# sb-sonata-headers1.net
KiCad netlist of a schematic drawn in Altium Designer
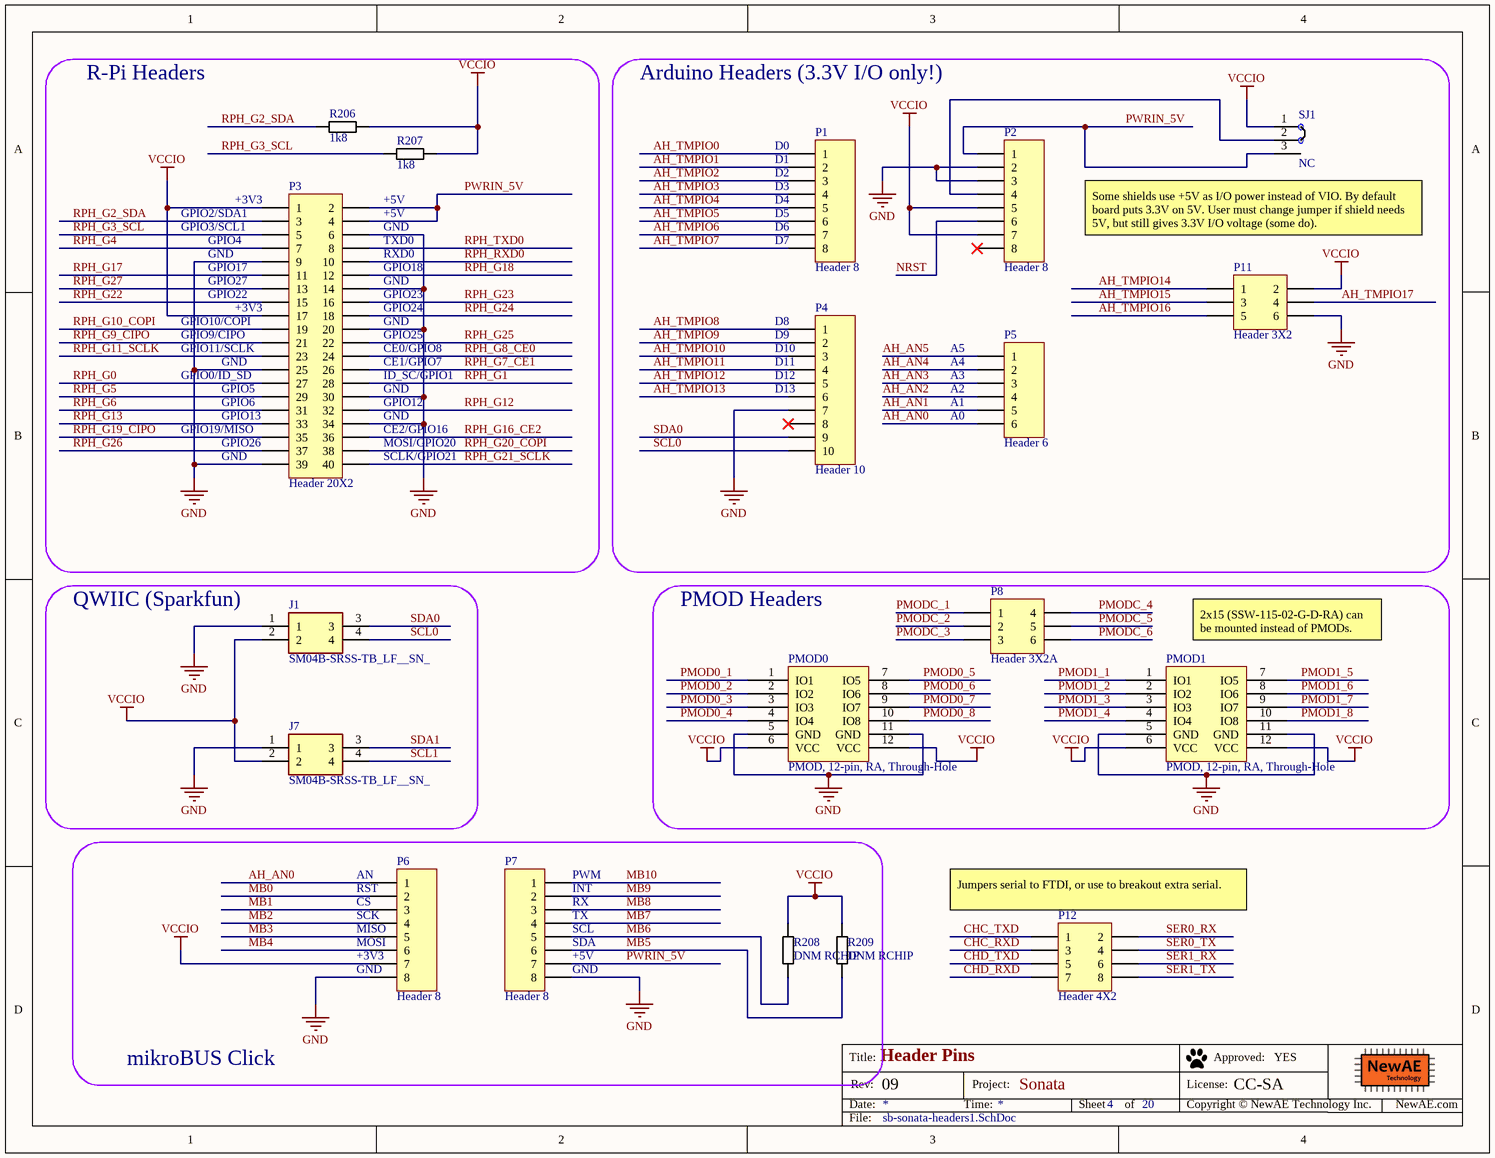
[diagram p0: sb-sonata-headers1.SchDoc]

(export (version "E")
  (design (tool "Eeschema 10.0.6"))
  (components
    (comp (ref "J1")
      (value "SM04B-SRSS-TB_LF__SN_")
      (footprint "SM04B-SRSS-TB(LFSN)")
      (description "Connector")
      (fields (field (name "MANUFACTURER_PART_NUMBER") "SM04B-SRSS-TB(LF)(SN)"))
      (libsource (lib "*") (part "SM04B-SRSS-TB_LF__SN_"))
    )
    (comp (ref "J7")
      (value "SM04B-SRSS-TB_LF__SN_")
      (footprint "SM04B-SRSS-TB(LFSN)")
      (description "Connector")
      (fields (field (name "MANUFACTURER_PART_NUMBER") "SM04B-SRSS-TB(LF)(SN)"))
      (libsource (lib "*") (part "SM04B-SRSS-TB_LF__SN_"))
    )
    (comp (ref "P1")
      (value "Header 8")
      (footprint "HDR1X8_SLW-108-01-T-S")
      (description "Header, 8-Pin")
      (fields (field (name "PUBLISHER") "Altium Limited"))
      (libsource (lib "") (part "Header 8_1"))
    )
    (comp (ref "P2")
      (value "Header 8")
      (footprint "HDR1X8_SLW-108-01-T-S")
      (description "Header, 8-Pin")
      (fields (field (name "PUBLISHER") "Altium Limited"))
      (libsource (lib "") (part "Header 8_1"))
    )
    (comp (ref "P3")
      (value "Header 20X2")
      (footprint "HDR2X20_861400402YO2LF")
      (description "Header, 20-Pin, Dual row")
      (fields (field (name "PUBLISHER") "Altium Limited"))
      (libsource (lib "Miscellaneous Connectors") (part "Header 20X2"))
    )
    (comp (ref "P4")
      (value "Header 10")
      (footprint "HDR1X10_SLW-110-01-T-S")
      (description "Header, 10-Pin")
      (fields (field (name "PUBLISHER") "Altium Limited"))
      (libsource (lib "Miscellaneous Connectors") (part "Header 10"))
    )
    (comp (ref "P5")
      (value "Header 6")
      (footprint "HDR1X6_SLW-106-01-T-S")
      (description "Header, 6-Pin")
      (fields (field (name "PUBLISHER") "Altium Limited"))
      (libsource (lib "Miscellaneous Connectors") (part "Header 6"))
    )
    (comp (ref "P6")
      (value "Header 8")
      (footprint "HDR1X8_SLW-108-01-T-S")
      (description "Header, 8-Pin")
      (fields (field (name "PUBLISHER") "Altium Limited"))
      (libsource (lib "") (part "Header 8_1"))
    )
    (comp (ref "P7")
      (value "Header 8")
      (footprint "HDR1X8_SLW-108-01-T-S")
      (description "Header, 8-Pin")
      (fields (field (name "PUBLISHER") "Altium Limited"))
      (libsource (lib "Miscellaneous Connectors") (part "Header 8"))
    )
    (comp (ref "P8")
      (value "Header 3X2A")
      (footprint "HDR2X3_CEN")
      (description "Header, 3-Pin, Dual row")
      (fields (field (name "PUBLISHER") "Altium Limited"))
      (libsource (lib "Miscellaneous Connectors") (part "Header 3X2A"))
    )
    (comp (ref "P11")
      (value "Header 3X2")
      (footprint "HDR2X3_XG8T-0641")
      (description "Header, 3-Pin, Dual row")
      (fields (field (name "PUBLISHER") "Altium Limited"))
      (libsource (lib "Miscellaneous Connectors") (part "Header 3X2"))
    )
    (comp (ref "P12")
      (value "Header 4X2")
      (footprint "HDR2X4_XG8T-0841")
      (description "Header, 4-Pin, Dual row")
      (fields (field (name "PUBLISHER") "Altium Limited"))
      (libsource (lib "Miscellaneous Connectors") (part "Header 4X2"))
    )
    (comp (ref "PMOD0")
      (value "PMOD, 12-pin, RA, Through-Hole")
      (footprint "SAMTEC_SSW_106_02_X_D_RA_PMOD")
      (fields (field (name "PART NUMBER") "PMOD_2ROW_FEMALERATH"))
      (libsource (lib "NewAE_AltiumLib") (part "12PIN_RA_FEMALE"))
    )
    (comp (ref "PMOD1")
      (value "PMOD, 12-pin, RA, Through-Hole")
      (footprint "SAMTEC_SSW_106_02_X_D_RA_PMOD")
      (fields (field (name "PART NUMBER") "PMOD_2ROW_FEMALERATH"))
      (libsource (lib "NewAE_AltiumLib") (part "12PIN_RA_FEMALE"))
    )
    (comp (ref "R206")
      (value "1k8")
      (footprint "RESC1608X55N")
      (description "1k8 res, 0603, 1%, 1/10W")
      (fields (field (name "PART NUMBER") "RCHIP-1K8-0603") (field (name "TOLERANCE") "1%"))
      (libsource (lib "") (part "RES-EU_1"))
    )
    (comp (ref "R207")
      (value "1k8")
      (footprint "RESC1608X55N")
      (description "1k8 res, 0603, 1%, 1/10W")
      (fields (field (name "PART NUMBER") "RCHIP-1K8-0603") (field (name "TOLERANCE") "1%"))
      (libsource (lib "") (part "RES-EU_1"))
    )
    (comp (ref "R208")
      (value "DNM RCHIP")
      (footprint "RESC1608X55N")
      (description "Do Not Mount Resistor")
      (fields (field (name "PART NUMBER") "RCHIP-DNM-0603"))
      (libsource (lib "NewAE_AltiumLib") (part "RES-EU"))
    )
    (comp (ref "R209")
      (value "DNM RCHIP")
      (footprint "RESC1608X55N")
      (description "Do Not Mount Resistor")
      (fields (field (name "PART NUMBER") "RCHIP-DNM-0603"))
      (libsource (lib "NewAE_AltiumLib") (part "RES-EU"))
    )
    (comp (ref "SJ1")
      (value "NC")
      (footprint "SJ_3S_NC12")
      (description "Solder Jumper, NC")
      (fields (field (name "PART NUMBER") "SJ_3S_12JMP"))
      (libsource (lib "NewAE_AltiumLib") (part "SJ_3S_12JMP"))
    )
  )
  (nets
    (net (code "1") (name "/AH_AN0") (class "Default")
      (node (ref "P5") (pin "6") (pinfunction "6_6") (pintype "passive"))
      (node (ref "P6") (pin "1") (pinfunction "1_1") (pintype "passive"))
    )
    (net (code "2") (name "/AH_AN1") (class "Default")
      (node (ref "P5") (pin "5") (pinfunction "5_5") (pintype "passive"))
    )
    (net (code "3") (name "/AH_AN2") (class "Default")
      (node (ref "P5") (pin "4") (pinfunction "4_4") (pintype "passive"))
    )
    (net (code "4") (name "/AH_AN3") (class "Default")
      (node (ref "P5") (pin "3") (pinfunction "3_3") (pintype "passive"))
    )
    (net (code "5") (name "/AH_AN4") (class "Default")
      (node (ref "P5") (pin "2") (pinfunction "2_2") (pintype "passive"))
    )
    (net (code "6") (name "/AH_AN5") (class "Default")
      (node (ref "P5") (pin "1") (pinfunction "1_1") (pintype "passive"))
    )
    (net (code "7") (name "/AH_TMPIO0") (class "Default")
      (node (ref "P1") (pin "1") (pinfunction "1_1") (pintype "passive"))
    )
    (net (code "8") (name "/AH_TMPIO1") (class "Default")
      (node (ref "P1") (pin "2") (pinfunction "2_2") (pintype "passive"))
    )
    (net (code "9") (name "/AH_TMPIO2") (class "Default")
      (node (ref "P1") (pin "3") (pinfunction "3_3") (pintype "passive"))
    )
    (net (code "10") (name "/AH_TMPIO3") (class "Default")
      (node (ref "P1") (pin "4") (pinfunction "4_4") (pintype "passive"))
    )
    (net (code "11") (name "/AH_TMPIO4") (class "Default")
      (node (ref "P1") (pin "5") (pinfunction "5_5") (pintype "passive"))
    )
    (net (code "12") (name "/AH_TMPIO5") (class "Default")
      (node (ref "P1") (pin "6") (pinfunction "6_6") (pintype "passive"))
    )
    (net (code "13") (name "/AH_TMPIO6") (class "Default")
      (node (ref "P1") (pin "7") (pinfunction "7_7") (pintype "passive"))
    )
    (net (code "14") (name "/AH_TMPIO7") (class "Default")
      (node (ref "P1") (pin "8") (pinfunction "8_8") (pintype "passive"))
    )
    (net (code "15") (name "/AH_TMPIO8") (class "Default")
      (node (ref "P4") (pin "1") (pinfunction "1_1") (pintype "passive"))
    )
    (net (code "16") (name "/AH_TMPIO9") (class "Default")
      (node (ref "P4") (pin "2") (pinfunction "2_2") (pintype "passive"))
    )
    (net (code "17") (name "/AH_TMPIO10") (class "Default")
      (node (ref "P4") (pin "3") (pinfunction "3_3") (pintype "passive"))
    )
    (net (code "18") (name "/AH_TMPIO11") (class "Default")
      (node (ref "P4") (pin "4") (pinfunction "4_4") (pintype "passive"))
    )
    (net (code "19") (name "/AH_TMPIO12") (class "Default")
      (node (ref "P4") (pin "5") (pinfunction "5_5") (pintype "passive"))
    )
    (net (code "20") (name "/AH_TMPIO13") (class "Default")
      (node (ref "P4") (pin "6") (pinfunction "6_6") (pintype "passive"))
    )
    (net (code "21") (name "/AH_TMPIO14") (class "Default")
      (node (ref "P11") (pin "1") (pinfunction "1_1") (pintype "passive"))
    )
    (net (code "22") (name "/AH_TMPIO15") (class "Default")
      (node (ref "P11") (pin "3") (pinfunction "3_3") (pintype "passive"))
    )
    (net (code "23") (name "/AH_TMPIO16") (class "Default")
      (node (ref "P11") (pin "5") (pinfunction "5_5") (pintype "passive"))
    )
    (net (code "24") (name "/AH_TMPIO17") (class "Default")
      (node (ref "P11") (pin "4") (pinfunction "4_4") (pintype "passive"))
    )
    (net (code "25") (name "/CHC_RXD") (class "Default")
      (node (ref "P12") (pin "3") (pinfunction "3_3") (pintype "passive"))
    )
    (net (code "26") (name "/CHC_TXD") (class "Default")
      (node (ref "P12") (pin "1") (pinfunction "1_1") (pintype "passive"))
    )
    (net (code "27") (name "/CHD_RXD") (class "Default")
      (node (ref "P12") (pin "7") (pinfunction "7_7") (pintype "passive"))
    )
    (net (code "28") (name "/CHD_TXD") (class "Default")
      (node (ref "P12") (pin "5") (pinfunction "5_5") (pintype "passive"))
    )
    (net (code "29") (name "/MB0") (class "Default")
      (node (ref "P6") (pin "2") (pinfunction "2_2") (pintype "passive"))
    )
    (net (code "30") (name "/MB1") (class "Default")
      (node (ref "P6") (pin "3") (pinfunction "3_3") (pintype "passive"))
    )
    (net (code "31") (name "/MB2") (class "Default")
      (node (ref "P6") (pin "4") (pinfunction "4_4") (pintype "passive"))
    )
    (net (code "32") (name "/MB3") (class "Default")
      (node (ref "P6") (pin "5") (pinfunction "5_5") (pintype "passive"))
    )
    (net (code "33") (name "/MB4") (class "Default")
      (node (ref "P6") (pin "6") (pinfunction "6_6") (pintype "passive"))
    )
    (net (code "34") (name "/MB5") (class "Default")
      (node (ref "P7") (pin "6") (pinfunction "6_6") (pintype "passive"))
      (node (ref "R209") (pin "2") (pinfunction "2_2") (pintype "passive"))
    )
    (net (code "35") (name "/MB6") (class "Default")
      (node (ref "P7") (pin "5") (pinfunction "5_5") (pintype "passive"))
      (node (ref "R208") (pin "2") (pinfunction "2_2") (pintype "passive"))
    )
    (net (code "36") (name "/MB7") (class "Default")
      (node (ref "P7") (pin "4") (pinfunction "4_4") (pintype "passive"))
    )
    (net (code "37") (name "/MB8") (class "Default")
      (node (ref "P7") (pin "3") (pinfunction "3_3") (pintype "passive"))
    )
    (net (code "38") (name "/MB9") (class "Default")
      (node (ref "P7") (pin "2") (pinfunction "2_2") (pintype "passive"))
    )
    (net (code "39") (name "/MB10") (class "Default")
      (node (ref "P7") (pin "1") (pinfunction "1_1") (pintype "passive"))
    )
    (net (code "40") (name "/NRST") (class "Default")
      (node (ref "P2") (pin "6") (pinfunction "6_6") (pintype "passive"))
    )
    (net (code "41") (name "/PMOD0_1") (class "Default")
      (node (ref "PMOD0") (pin "1") (pinfunction "IO1_1") (pintype "passive"))
    )
    (net (code "42") (name "/PMOD0_2") (class "Default")
      (node (ref "PMOD0") (pin "2") (pinfunction "IO2_2") (pintype "passive"))
    )
    (net (code "43") (name "/PMOD0_3") (class "Default")
      (node (ref "PMOD0") (pin "3") (pinfunction "IO3_3") (pintype "passive"))
    )
    (net (code "44") (name "/PMOD0_4") (class "Default")
      (node (ref "PMOD0") (pin "4") (pinfunction "IO4_4") (pintype "passive"))
    )
    (net (code "45") (name "/PMOD0_5") (class "Default")
      (node (ref "PMOD0") (pin "7") (pinfunction "IO5_7") (pintype "passive"))
    )
    (net (code "46") (name "/PMOD0_6") (class "Default")
      (node (ref "PMOD0") (pin "8") (pinfunction "IO6_8") (pintype "passive"))
    )
    (net (code "47") (name "/PMOD0_7") (class "Default")
      (node (ref "PMOD0") (pin "9") (pinfunction "IO7_9") (pintype "passive"))
    )
    (net (code "48") (name "/PMOD0_8") (class "Default")
      (node (ref "PMOD0") (pin "10") (pinfunction "IO8_10") (pintype "passive"))
    )
    (net (code "49") (name "/PMOD1_1") (class "Default")
      (node (ref "PMOD1") (pin "1") (pinfunction "IO1_1") (pintype "passive"))
    )
    (net (code "50") (name "/PMOD1_2") (class "Default")
      (node (ref "PMOD1") (pin "2") (pinfunction "IO2_2") (pintype "passive"))
    )
    (net (code "51") (name "/PMOD1_3") (class "Default")
      (node (ref "PMOD1") (pin "3") (pinfunction "IO3_3") (pintype "passive"))
    )
    (net (code "52") (name "/PMOD1_4") (class "Default")
      (node (ref "PMOD1") (pin "4") (pinfunction "IO4_4") (pintype "passive"))
    )
    (net (code "53") (name "/PMOD1_5") (class "Default")
      (node (ref "PMOD1") (pin "7") (pinfunction "IO5_7") (pintype "passive"))
    )
    (net (code "54") (name "/PMOD1_6") (class "Default")
      (node (ref "PMOD1") (pin "8") (pinfunction "IO6_8") (pintype "passive"))
    )
    (net (code "55") (name "/PMOD1_7") (class "Default")
      (node (ref "PMOD1") (pin "9") (pinfunction "IO7_9") (pintype "passive"))
    )
    (net (code "56") (name "/PMOD1_8") (class "Default")
      (node (ref "PMOD1") (pin "10") (pinfunction "IO8_10") (pintype "passive"))
    )
    (net (code "57") (name "/PMODC_1") (class "Default")
      (node (ref "P8") (pin "1") (pinfunction "1_1") (pintype "passive"))
    )
    (net (code "58") (name "/PMODC_2") (class "Default")
      (node (ref "P8") (pin "2") (pinfunction "2_2") (pintype "passive"))
    )
    (net (code "59") (name "/PMODC_3") (class "Default")
      (node (ref "P8") (pin "3") (pinfunction "3_3") (pintype "passive"))
    )
    (net (code "60") (name "/PMODC_4") (class "Default")
      (node (ref "P8") (pin "4") (pinfunction "4_4") (pintype "passive"))
    )
    (net (code "61") (name "/PMODC_5") (class "Default")
      (node (ref "P8") (pin "5") (pinfunction "5_5") (pintype "passive"))
    )
    (net (code "62") (name "/PMODC_6") (class "Default")
      (node (ref "P8") (pin "6") (pinfunction "6_6") (pintype "passive"))
    )
    (net (code "63") (name "/PWRIN_5V") (class "Default")
      (node (ref "P2") (pin "1") (pinfunction "1_1") (pintype "passive"))
      (node (ref "P3") (pin "2") (pinfunction "2_2") (pintype "passive"))
      (node (ref "P3") (pin "4") (pinfunction "4_4") (pintype "passive"))
      (node (ref "P7") (pin "7") (pinfunction "7_7") (pintype "passive"))
      (node (ref "SJ1") (pin "3") (pinfunction "3_3") (pintype "passive"))
    )
    (net (code "64") (name "/RPH_G0") (class "Default")
      (node (ref "P3") (pin "27") (pinfunction "27_27") (pintype "passive"))
    )
    (net (code "65") (name "/RPH_G1") (class "Default")
      (node (ref "P3") (pin "28") (pinfunction "28_28") (pintype "passive"))
    )
    (net (code "66") (name "/RPH_G2_SDA") (class "Default")
      (node (ref "P3") (pin "3") (pinfunction "3_3") (pintype "passive"))
      (node (ref "R206") (pin "1") (pinfunction "1_1") (pintype "passive"))
    )
    (net (code "67") (name "/RPH_G3_SCL") (class "Default")
      (node (ref "P3") (pin "5") (pinfunction "5_5") (pintype "passive"))
      (node (ref "R207") (pin "1") (pinfunction "1_1") (pintype "passive"))
    )
    (net (code "68") (name "/RPH_G4") (class "Default")
      (node (ref "P3") (pin "7") (pinfunction "7_7") (pintype "passive"))
    )
    (net (code "69") (name "/RPH_G5") (class "Default")
      (node (ref "P3") (pin "29") (pinfunction "29_29") (pintype "passive"))
    )
    (net (code "70") (name "/RPH_G6") (class "Default")
      (node (ref "P3") (pin "31") (pinfunction "31_31") (pintype "passive"))
    )
    (net (code "71") (name "/RPH_G7_CE1") (class "Default")
      (node (ref "P3") (pin "26") (pinfunction "26_26") (pintype "passive"))
    )
    (net (code "72") (name "/RPH_G8_CE0") (class "Default")
      (node (ref "P3") (pin "24") (pinfunction "24_24") (pintype "passive"))
    )
    (net (code "73") (name "/RPH_G9_CIPO") (class "Default")
      (node (ref "P3") (pin "21") (pinfunction "21_21") (pintype "passive"))
    )
    (net (code "74") (name "/RPH_G10_COPI") (class "Default")
      (node (ref "P3") (pin "19") (pinfunction "19_19") (pintype "passive"))
    )
    (net (code "75") (name "/RPH_G11_SCLK") (class "Default")
      (node (ref "P3") (pin "23") (pinfunction "23_23") (pintype "passive"))
    )
    (net (code "76") (name "/RPH_G12") (class "Default")
      (node (ref "P3") (pin "32") (pinfunction "32_32") (pintype "passive"))
    )
    (net (code "77") (name "/RPH_G13") (class "Default")
      (node (ref "P3") (pin "33") (pinfunction "33_33") (pintype "passive"))
    )
    (net (code "78") (name "/RPH_G16_CE2") (class "Default")
      (node (ref "P3") (pin "36") (pinfunction "36_36") (pintype "passive"))
    )
    (net (code "79") (name "/RPH_G17") (class "Default")
      (node (ref "P3") (pin "11") (pinfunction "11_11") (pintype "passive"))
    )
    (net (code "80") (name "/RPH_G18") (class "Default")
      (node (ref "P3") (pin "12") (pinfunction "12_12") (pintype "passive"))
    )
    (net (code "81") (name "/RPH_G19_CIPO") (class "Default")
      (node (ref "P3") (pin "35") (pinfunction "35_35") (pintype "passive"))
    )
    (net (code "82") (name "/RPH_G20_COPI") (class "Default")
      (node (ref "P3") (pin "38") (pinfunction "38_38") (pintype "passive"))
    )
    (net (code "83") (name "/RPH_G21_SCLK") (class "Default")
      (node (ref "P3") (pin "40") (pinfunction "40_40") (pintype "passive"))
    )
    (net (code "84") (name "/RPH_G22") (class "Default")
      (node (ref "P3") (pin "15") (pinfunction "15_15") (pintype "passive"))
    )
    (net (code "85") (name "/RPH_G23") (class "Default")
      (node (ref "P3") (pin "16") (pinfunction "16_16") (pintype "passive"))
    )
    (net (code "86") (name "/RPH_G24") (class "Default")
      (node (ref "P3") (pin "18") (pinfunction "18_18") (pintype "passive"))
    )
    (net (code "87") (name "/RPH_G25") (class "Default")
      (node (ref "P3") (pin "22") (pinfunction "22_22") (pintype "passive"))
    )
    (net (code "88") (name "/RPH_G26") (class "Default")
      (node (ref "P3") (pin "37") (pinfunction "37_37") (pintype "passive"))
    )
    (net (code "89") (name "/RPH_G27") (class "Default")
      (node (ref "P3") (pin "13") (pinfunction "13_13") (pintype "passive"))
    )
    (net (code "90") (name "/RPH_RXD0") (class "Default")
      (node (ref "P3") (pin "10") (pinfunction "10_10") (pintype "passive"))
    )
    (net (code "91") (name "/RPH_TXD0") (class "Default")
      (node (ref "P3") (pin "8") (pinfunction "8_8") (pintype "passive"))
    )
    (net (code "92") (name "/SCL0") (class "Default")
      (node (ref "J1") (pin "4") (pinfunction "4_4") (pintype "passive"))
      (node (ref "P4") (pin "10") (pinfunction "10_10") (pintype "passive"))
    )
    (net (code "93") (name "/SCL1") (class "Default")
      (node (ref "J7") (pin "4") (pinfunction "4_4") (pintype "passive"))
    )
    (net (code "94") (name "/SDA0") (class "Default")
      (node (ref "J1") (pin "3") (pinfunction "3_3") (pintype "passive"))
      (node (ref "P4") (pin "9") (pinfunction "9_9") (pintype "passive"))
    )
    (net (code "95") (name "/SDA1") (class "Default")
      (node (ref "J7") (pin "3") (pinfunction "3_3") (pintype "passive"))
    )
    (net (code "96") (name "/SER0_RX") (class "Default")
      (node (ref "P12") (pin "2") (pinfunction "2_2") (pintype "passive"))
    )
    (net (code "97") (name "/SER0_TX") (class "Default")
      (node (ref "P12") (pin "4") (pinfunction "4_4") (pintype "passive"))
    )
    (net (code "98") (name "/SER1_RX") (class "Default")
      (node (ref "P12") (pin "6") (pinfunction "6_6") (pintype "passive"))
    )
    (net (code "99") (name "/SER1_TX") (class "Default")
      (node (ref "P12") (pin "8") (pinfunction "8_8") (pintype "passive"))
    )
    (net (code "100") (name "GND") (class "Default")
      (node (ref "J1") (pin "1") (pinfunction "1_1") (pintype "passive"))
      (node (ref "J7") (pin "1") (pinfunction "1_1") (pintype "passive"))
      (node (ref "P11") (pin "6") (pinfunction "6_6") (pintype "passive"))
      (node (ref "P2") (pin "2") (pinfunction "2_2") (pintype "passive"))
      (node (ref "P2") (pin "3") (pinfunction "3_3") (pintype "passive"))
      (node (ref "P3") (pin "14") (pinfunction "14_14") (pintype "passive"))
      (node (ref "P3") (pin "20") (pinfunction "20_20") (pintype "passive"))
      (node (ref "P3") (pin "25") (pinfunction "25_25") (pintype "passive"))
      (node (ref "P3") (pin "30") (pinfunction "30_30") (pintype "passive"))
      (node (ref "P3") (pin "34") (pinfunction "34_34") (pintype "passive"))
      (node (ref "P3") (pin "39") (pinfunction "39_39") (pintype "passive"))
      (node (ref "P3") (pin "6") (pinfunction "6_6") (pintype "passive"))
      (node (ref "P3") (pin "9") (pinfunction "9_9") (pintype "passive"))
      (node (ref "P4") (pin "7") (pinfunction "7_7") (pintype "passive"))
      (node (ref "P6") (pin "8") (pinfunction "8_8") (pintype "passive"))
      (node (ref "P7") (pin "8") (pinfunction "8_8") (pintype "passive"))
      (node (ref "PMOD0") (pin "11") (pinfunction "GND_11") (pintype "passive"))
      (node (ref "PMOD0") (pin "5") (pinfunction "GND_5") (pintype "passive"))
      (node (ref "PMOD1") (pin "11") (pinfunction "GND_11") (pintype "passive"))
      (node (ref "PMOD1") (pin "5") (pinfunction "GND_5") (pintype "passive"))
    )
    (net (code "101") (name "Net-(P2-Pad4)") (class "Default")
      (node (ref "P2") (pin "4") (pinfunction "4_4") (pintype "passive"))
      (node (ref "SJ1") (pin "2") (pinfunction "2_2") (pintype "passive"))
    )
    (net (code "102") (name "VCCIO") (class "Default")
      (node (ref "J1") (pin "2") (pinfunction "2_2") (pintype "passive"))
      (node (ref "J7") (pin "2") (pinfunction "2_2") (pintype "passive"))
      (node (ref "P11") (pin "2") (pinfunction "2_2") (pintype "passive"))
      (node (ref "P2") (pin "5") (pinfunction "5_5") (pintype "passive"))
      (node (ref "P2") (pin "7") (pinfunction "7_7") (pintype "passive"))
      (node (ref "P3") (pin "1") (pinfunction "1_1") (pintype "passive"))
      (node (ref "P3") (pin "17") (pinfunction "17_17") (pintype "passive"))
      (node (ref "P6") (pin "7") (pinfunction "7_7") (pintype "passive"))
      (node (ref "PMOD0") (pin "12") (pinfunction "VCC_12") (pintype "passive"))
      (node (ref "PMOD0") (pin "6") (pinfunction "VCC_6") (pintype "passive"))
      (node (ref "PMOD1") (pin "12") (pinfunction "VCC_12") (pintype "passive"))
      (node (ref "PMOD1") (pin "6") (pinfunction "VCC_6") (pintype "passive"))
      (node (ref "R206") (pin "2") (pinfunction "2_2") (pintype "passive"))
      (node (ref "R207") (pin "2") (pinfunction "2_2") (pintype "passive"))
      (node (ref "R208") (pin "1") (pinfunction "1_1") (pintype "passive"))
      (node (ref "R209") (pin "1") (pinfunction "1_1") (pintype "passive"))
      (node (ref "SJ1") (pin "1") (pinfunction "1_1") (pintype "passive"))
    )
    (net (code "103") (name "unconnected-(P2-Pad8)") (class "Default")
      (node (ref "P2") (pin "8") (pinfunction "8_8") (pintype "passive+no_connect"))
    )
    (net (code "104") (name "unconnected-(P4-Pad8)") (class "Default")
      (node (ref "P4") (pin "8") (pinfunction "8_8") (pintype "passive+no_connect"))
    )
  )
)
